# MCU.net
KiCad netlist of a schematic drawn in Altium Designer
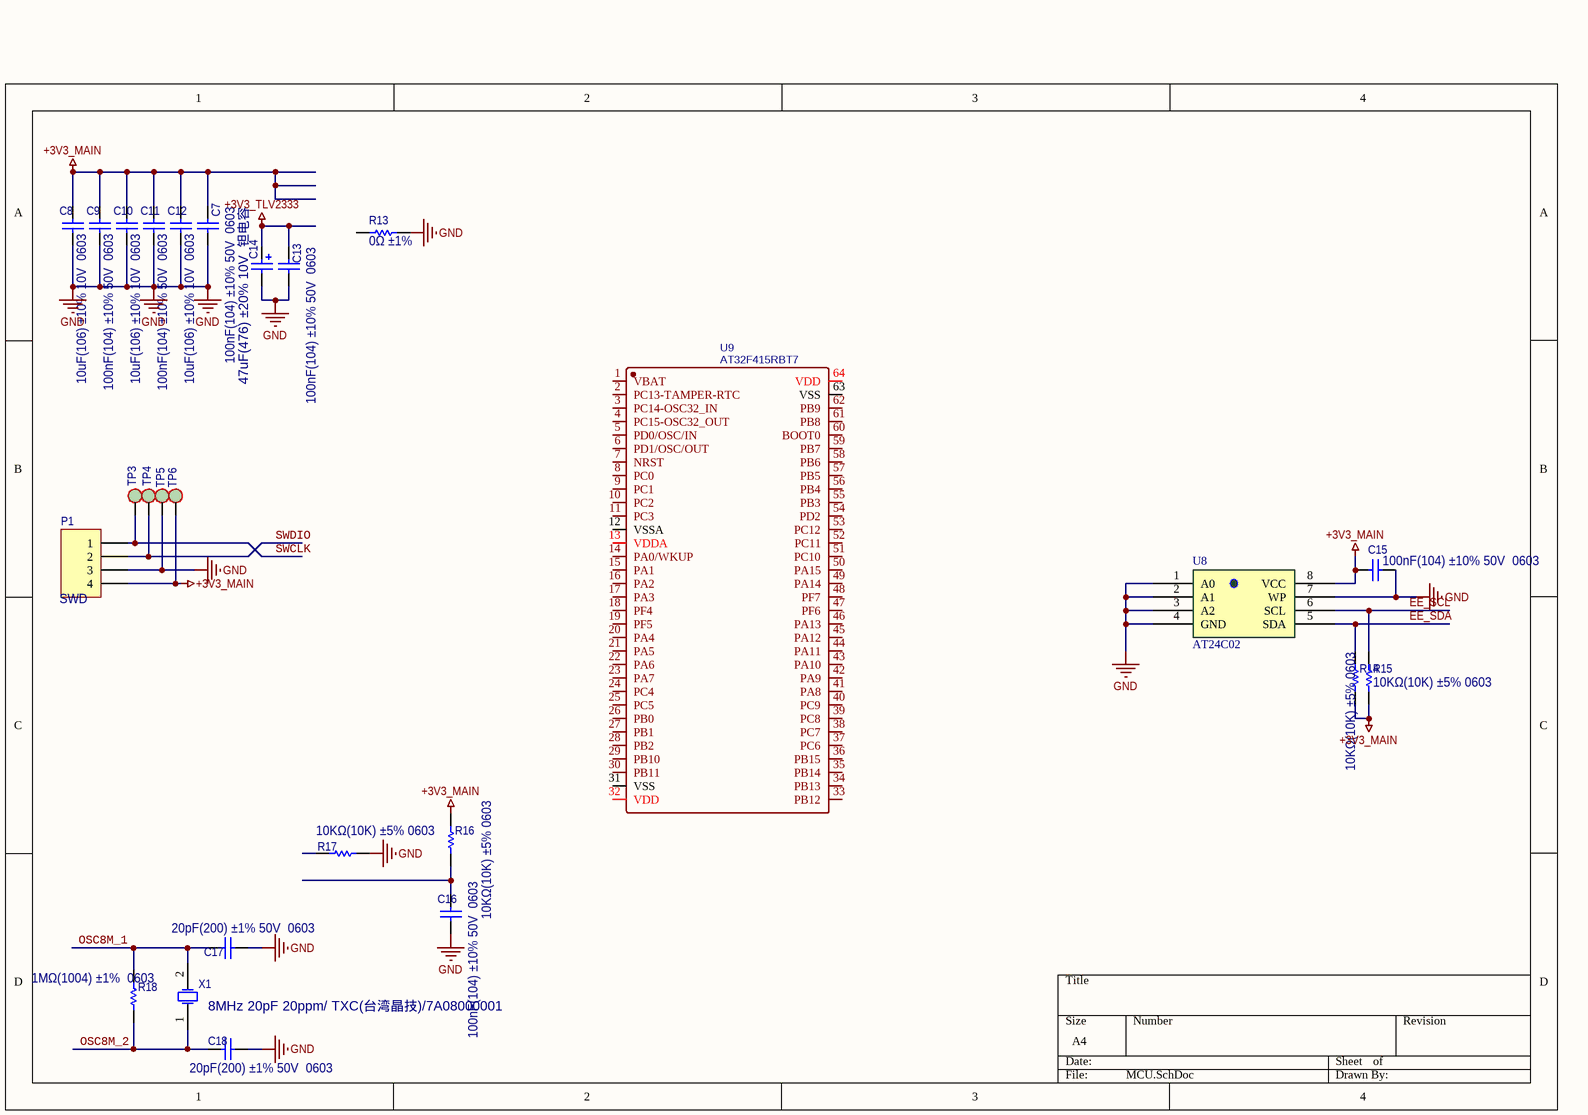
[diagram p0: MCU.SchDoc]

(export (version "E")
  (design (tool "Eeschema 10.0.6"))
  (components
    (comp (ref "C7")
      (value "100nF(104) ±10% 50V  0603")
      (footprint "C0603")
      (description "0603贴片电容")
      (fields (field (name "PUBLISHER") "Altium Limited"))
      (libsource (lib "Miscellaneous Devices") (part "Cap"))
    )
    (comp (ref "C8")
      (value "10uF(106) ±10% 10V  0603")
      (footprint "C0603")
      (description "0603贴片电容")
      (fields (field (name "PUBLISHER") "Altium Limited"))
      (libsource (lib "Miscellaneous Devices") (part "Cap"))
    )
    (comp (ref "C9")
      (value "100nF(104) ±10% 50V  0603")
      (footprint "C0603")
      (description "0603贴片电容")
      (fields (field (name "PUBLISHER") "Altium Limited"))
      (libsource (lib "Miscellaneous Devices") (part "Cap"))
    )
    (comp (ref "C10")
      (value "10uF(106) ±10% 10V  0603")
      (footprint "C0603")
      (description "0603贴片电容")
      (fields (field (name "PUBLISHER") "Altium Limited"))
      (libsource (lib "Miscellaneous Devices") (part "Cap"))
    )
    (comp (ref "C11")
      (value "100nF(104) ±10% 50V  0603")
      (footprint "C0603")
      (description "0603贴片电容")
      (fields (field (name "PUBLISHER") "Altium Limited"))
      (libsource (lib "Miscellaneous Devices") (part "Cap"))
    )
    (comp (ref "C12")
      (value "10uF(106) ±10% 10V  0603")
      (footprint "C0603")
      (description "0603贴片电容")
      (fields (field (name "PUBLISHER") "Altium Limited"))
      (libsource (lib "Miscellaneous Devices") (part "Cap"))
    )
    (comp (ref "C13")
      (value "100nF(104) ±10% 50V  0603")
      (footprint "C0603")
      (description "0603贴片电容")
      (fields (field (name "PUBLISHER") "Altium Limited"))
      (libsource (lib "Miscellaneous Devices") (part "Cap"))
    )
    (comp (ref "C14")
      (value "47uF(476) ±20% 10V  钽电容")
      (footprint "CASE-B_3528")
      (description "CASE_B 3528钽电容")
      (fields (field (name "PUBLISHER") "Altium Limited"))
      (libsource (lib "Miscellaneous Devices") (part "Cap Pol2"))
    )
    (comp (ref "C15")
      (value "100nF(104) ±10% 50V  0603")
      (footprint "C0603")
      (description "0603贴片电容")
      (fields (field (name "PUBLISHER") "Altium Limited"))
      (libsource (lib "Miscellaneous Devices") (part "Cap"))
    )
    (comp (ref "C16")
      (value "100nF(104) ±10% 50V  0603")
      (footprint "C0603")
      (description "0603贴片电容")
      (fields (field (name "PUBLISHER") "Altium Limited"))
      (libsource (lib "Miscellaneous Devices") (part "Cap"))
    )
    (comp (ref "C17")
      (value "20pF(200) ±1% 50V  0603")
      (footprint "C0603")
      (description "0603贴片电容")
      (fields (field (name "PUBLISHER") "Altium Limited"))
      (libsource (lib "Miscellaneous Devices") (part "Cap"))
    )
    (comp (ref "C18")
      (value "20pF(200) ±1% 50V  0603")
      (footprint "C0603")
      (description "0603贴片电容")
      (fields (field (name "PUBLISHER") "Altium Limited"))
      (libsource (lib "Miscellaneous Devices") (part "Cap"))
    )
    (comp (ref "P1")
      (value "SWD")
      (footprint "HDR1X4")
      (description "编程下载口")
      (fields (field (name "PUBLISHER") "Altium Limited"))
      (libsource (lib "Miscellaneous Connectors") (part "Header 4"))
    )
    (comp (ref "R13")
      (value "0Ω ±1%")
      (footprint "R0603")
      (description "0603贴片电阻")
      (fields (field (name "PUBLISHER") "Altium Limited"))
      (libsource (lib "Miscellaneous Devices") (part "Res1"))
    )
    (comp (ref "R14")
      (value "10KΩ(10K) ±5% 0603")
      (footprint "R0603")
      (description "0603贴片电阻")
      (fields (field (name "PUBLISHER") "Altium Limited"))
      (libsource (lib "Miscellaneous Devices") (part "Res1"))
    )
    (comp (ref "R15")
      (value "10KΩ(10K) ±5% 0603")
      (footprint "R0603")
      (description "0603贴片电阻")
      (fields (field (name "PUBLISHER") "Altium Limited"))
      (libsource (lib "Miscellaneous Devices") (part "Res1"))
    )
    (comp (ref "R16")
      (value "10KΩ(10K) ±5% 0603")
      (footprint "R0603")
      (description "0603贴片电阻")
      (fields (field (name "PUBLISHER") "Altium Limited"))
      (libsource (lib "Miscellaneous Devices") (part "Res1"))
    )
    (comp (ref "R17")
      (value "10KΩ(10K) ±5% 0603")
      (footprint "R0603")
      (description "0603贴片电阻")
      (fields (field (name "PUBLISHER") "Altium Limited"))
      (libsource (lib "Miscellaneous Devices") (part "Res1"))
    )
    (comp (ref "R18")
      (value "1MΩ(1004) ±1%  0603")
      (footprint "R0603")
      (description "0603贴片电阻")
      (fields (field (name "PUBLISHER") "Altium Limited"))
      (libsource (lib "Miscellaneous Devices") (part "Res1"))
    )
    (comp (ref "TP3") (value "NC") (footprint "TP") (description "测试点") (libsource (lib "Tek") (part "TP")))
    (comp (ref "TP4") (value "NC") (footprint "TP") (description "测试点") (libsource (lib "Tek") (part "TP")))
    (comp (ref "TP5") (value "NC") (footprint "TP") (description "测试点") (libsource (lib "Tek") (part "TP")))
    (comp (ref "TP6") (value "NC") (footprint "TP") (description "测试点") (libsource (lib "Tek") (part "TP")))
    (comp (ref "U8")
      (value "AT24C02")
      (footprint "SOIC-8_150mil")
      (description "非易失性存储器(ROM)")
      (libsource (lib "Tek") (part "24CXX"))
    )
    (comp (ref "U9")
      (value "AT32F415RBT7")
      (footprint "LQFP64")
      (fields (field (name "BOM_SUPPLIER PART") "C528433") (field (name "CONTRIBUTOR") "LCSC"))
      (libsource (lib "altium-import") (part "root_0_AT32F415RBT7_"))
    )
    (comp (ref "X1")
      (value "8MHz 20pF 20ppm/ TXC(台湾晶技)/7A08000001")
      (footprint "CRY5032_2P_SMT")
      (description "无源晶振  SMD-5032_2P")
      (fields (field (name "PUBLISHER") "ZL_A0OFFICE"))
      (libsource (lib "CommomDevices") (part "XTAL_SMD"))
    )
  )
  (nets
    (net (code "1") (name "+3V3_MAIN") (class "Default")
      (node (ref "C10") (pin "2") (pinfunction "2_2") (pintype "passive"))
      (node (ref "C11") (pin "2") (pinfunction "2_2") (pintype "passive"))
      (node (ref "C12") (pin "2") (pinfunction "2_2") (pintype "passive"))
      (node (ref "C15") (pin "2") (pinfunction "2_2") (pintype "passive"))
      (node (ref "C7") (pin "2") (pinfunction "2_2") (pintype "passive"))
      (node (ref "C8") (pin "2") (pinfunction "2_2") (pintype "passive"))
      (node (ref "C9") (pin "2") (pinfunction "2_2") (pintype "passive"))
      (node (ref "P1") (pin "4") (pinfunction "4_4") (pintype "passive"))
      (node (ref "R14") (pin "2") (pinfunction "2_2") (pintype "passive"))
      (node (ref "R15") (pin "2") (pinfunction "2_2") (pintype "passive"))
      (node (ref "R16") (pin "1") (pinfunction "1_1") (pintype "passive"))
      (node (ref "TP6") (pin "1") (pinfunction "0_1") (pintype "passive"))
      (node (ref "U8") (pin "8") (pinfunction "VCC_8") (pintype "passive"))
    )
    (net (code "2") (name "+3V3_TLV2333") (class "Default")
      (node (ref "C13") (pin "2") (pinfunction "2_2") (pintype "passive"))
      (node (ref "C14") (pin "1") (pinfunction "1_1") (pintype "passive"))
    )
    (net (code "3") (name "/EE_SCL") (class "Default")
      (node (ref "R15") (pin "1") (pinfunction "1_1") (pintype "passive"))
      (node (ref "U8") (pin "6") (pinfunction "SCL_6") (pintype "passive"))
    )
    (net (code "4") (name "/EE_SDA") (class "Default")
      (node (ref "R14") (pin "1") (pinfunction "1_1") (pintype "passive"))
      (node (ref "U8") (pin "5") (pinfunction "SDA_5") (pintype "passive"))
    )
    (net (code "5") (name "/OSC8M_1") (class "Default")
      (node (ref "C17") (pin "2") (pinfunction "2_2") (pintype "passive"))
      (node (ref "R18") (pin "1") (pinfunction "1_1") (pintype "passive"))
      (node (ref "X1") (pin "2") (pinfunction "2_2") (pintype "passive"))
    )
    (net (code "6") (name "/OSC8M_2") (class "Default")
      (node (ref "C18") (pin "2") (pinfunction "2_2") (pintype "passive"))
      (node (ref "R18") (pin "2") (pinfunction "2_2") (pintype "passive"))
      (node (ref "X1") (pin "1") (pinfunction "1_1") (pintype "passive"))
    )
    (net (code "7") (name "/SWCLK") (class "Default")
      (node (ref "P1") (pin "1") (pinfunction "1_1") (pintype "passive"))
      (node (ref "TP3") (pin "1") (pinfunction "0_1") (pintype "passive"))
    )
    (net (code "8") (name "/SWDIO") (class "Default")
      (node (ref "P1") (pin "2") (pinfunction "2_2") (pintype "passive"))
      (node (ref "TP4") (pin "1") (pinfunction "0_1") (pintype "passive"))
    )
    (net (code "9") (name "GND") (class "Default")
      (node (ref "C10") (pin "1") (pinfunction "1_1") (pintype "passive"))
      (node (ref "C11") (pin "1") (pinfunction "1_1") (pintype "passive"))
      (node (ref "C12") (pin "1") (pinfunction "1_1") (pintype "passive"))
      (node (ref "C13") (pin "1") (pinfunction "1_1") (pintype "passive"))
      (node (ref "C14") (pin "2") (pinfunction "2_2") (pintype "passive"))
      (node (ref "C15") (pin "1") (pinfunction "1_1") (pintype "passive"))
      (node (ref "C16") (pin "1") (pinfunction "1_1") (pintype "passive"))
      (node (ref "C17") (pin "1") (pinfunction "1_1") (pintype "passive"))
      (node (ref "C18") (pin "1") (pinfunction "1_1") (pintype "passive"))
      (node (ref "C7") (pin "1") (pinfunction "1_1") (pintype "passive"))
      (node (ref "C8") (pin "1") (pinfunction "1_1") (pintype "passive"))
      (node (ref "C9") (pin "1") (pinfunction "1_1") (pintype "passive"))
      (node (ref "P1") (pin "3") (pinfunction "3_3") (pintype "passive"))
      (node (ref "R13") (pin "1") (pinfunction "1_1") (pintype "passive"))
      (node (ref "R17") (pin "1") (pinfunction "1_1") (pintype "passive"))
      (node (ref "TP5") (pin "1") (pinfunction "0_1") (pintype "passive"))
      (node (ref "U8") (pin "1") (pinfunction "A0_1") (pintype "passive"))
      (node (ref "U8") (pin "2") (pinfunction "A1_2") (pintype "passive"))
      (node (ref "U8") (pin "3") (pinfunction "A2_3") (pintype "passive"))
      (node (ref "U8") (pin "4") (pinfunction "GND_4") (pintype "passive"))
      (node (ref "U8") (pin "7") (pinfunction "WP_7") (pintype "passive"))
    )
    (net (code "10") (name "Net-(C16-Pad2)") (class "Default")
      (node (ref "C16") (pin "2") (pinfunction "2_2") (pintype "passive"))
      (node (ref "R16") (pin "2") (pinfunction "2_2") (pintype "passive"))
    )
    (net (code "11") (name "unconnected-(R13-Pad2)") (class "Default")
      (node (ref "R13") (pin "2") (pinfunction "2_2") (pintype "passive"))
    )
    (net (code "12") (name "unconnected-(R17-Pad2)") (class "Default")
      (node (ref "R17") (pin "2") (pinfunction "2_2") (pintype "passive"))
    )
    (net (code "13") (name "unconnected-(U9-BOOT0-Pad60)") (class "Default")
      (node (ref "U9") (pin "60") (pinfunction "BOOT0_60") (pintype "passive"))
    )
    (net (code "14") (name "unconnected-(U9-NRST-Pad7)") (class "Default")
      (node (ref "U9") (pin "7") (pinfunction "NRST_7") (pintype "passive"))
    )
    (net (code "15") (name "unconnected-(U9-PA0{slash}WKUP-Pad14)") (class "Default")
      (node (ref "U9") (pin "14") (pinfunction "PA0/WKUP_14") (pintype "passive"))
    )
    (net (code "16") (name "unconnected-(U9-PA1-Pad15)") (class "Default")
      (node (ref "U9") (pin "15") (pinfunction "PA1_15") (pintype "passive"))
    )
    (net (code "17") (name "unconnected-(U9-PA2-Pad16)") (class "Default")
      (node (ref "U9") (pin "16") (pinfunction "PA2_16") (pintype "passive"))
    )
    (net (code "18") (name "unconnected-(U9-PA3-Pad17)") (class "Default")
      (node (ref "U9") (pin "17") (pinfunction "PA3_17") (pintype "passive"))
    )
    (net (code "19") (name "unconnected-(U9-PA4-Pad20)") (class "Default")
      (node (ref "U9") (pin "20") (pinfunction "PA4_20") (pintype "passive"))
    )
    (net (code "20") (name "unconnected-(U9-PA5-Pad21)") (class "Default")
      (node (ref "U9") (pin "21") (pinfunction "PA5_21") (pintype "passive"))
    )
    (net (code "21") (name "unconnected-(U9-PA6-Pad22)") (class "Default")
      (node (ref "U9") (pin "22") (pinfunction "PA6_22") (pintype "passive"))
    )
    (net (code "22") (name "unconnected-(U9-PA7-Pad23)") (class "Default")
      (node (ref "U9") (pin "23") (pinfunction "PA7_23") (pintype "passive"))
    )
    (net (code "23") (name "unconnected-(U9-PA8-Pad41)") (class "Default")
      (node (ref "U9") (pin "41") (pinfunction "PA8_41") (pintype "passive"))
    )
    (net (code "24") (name "unconnected-(U9-PA9-Pad42)") (class "Default")
      (node (ref "U9") (pin "42") (pinfunction "PA9_42") (pintype "passive"))
    )
    (net (code "25") (name "unconnected-(U9-PA10-Pad43)") (class "Default")
      (node (ref "U9") (pin "43") (pinfunction "PA10_43") (pintype "passive"))
    )
    (net (code "26") (name "unconnected-(U9-PA11-Pad44)") (class "Default")
      (node (ref "U9") (pin "44") (pinfunction "PA11_44") (pintype "passive"))
    )
    (net (code "27") (name "unconnected-(U9-PA12-Pad45)") (class "Default")
      (node (ref "U9") (pin "45") (pinfunction "PA12_45") (pintype "passive"))
    )
    (net (code "28") (name "unconnected-(U9-PA13-Pad46)") (class "Default")
      (node (ref "U9") (pin "46") (pinfunction "PA13_46") (pintype "passive"))
    )
    (net (code "29") (name "unconnected-(U9-PA14-Pad49)") (class "Default")
      (node (ref "U9") (pin "49") (pinfunction "PA14_49") (pintype "passive"))
    )
    (net (code "30") (name "unconnected-(U9-PA15-Pad50)") (class "Default")
      (node (ref "U9") (pin "50") (pinfunction "PA15_50") (pintype "passive"))
    )
    (net (code "31") (name "unconnected-(U9-PB0-Pad26)") (class "Default")
      (node (ref "U9") (pin "26") (pinfunction "PB0_26") (pintype "passive"))
    )
    (net (code "32") (name "unconnected-(U9-PB1-Pad27)") (class "Default")
      (node (ref "U9") (pin "27") (pinfunction "PB1_27") (pintype "passive"))
    )
    (net (code "33") (name "unconnected-(U9-PB2-Pad28)") (class "Default")
      (node (ref "U9") (pin "28") (pinfunction "PB2_28") (pintype "passive"))
    )
    (net (code "34") (name "unconnected-(U9-PB3-Pad55)") (class "Default")
      (node (ref "U9") (pin "55") (pinfunction "PB3_55") (pintype "passive"))
    )
    (net (code "35") (name "unconnected-(U9-PB4-Pad56)") (class "Default")
      (node (ref "U9") (pin "56") (pinfunction "PB4_56") (pintype "passive"))
    )
    (net (code "36") (name "unconnected-(U9-PB5-Pad57)") (class "Default")
      (node (ref "U9") (pin "57") (pinfunction "PB5_57") (pintype "passive"))
    )
    (net (code "37") (name "unconnected-(U9-PB6-Pad58)") (class "Default")
      (node (ref "U9") (pin "58") (pinfunction "PB6_58") (pintype "passive"))
    )
    (net (code "38") (name "unconnected-(U9-PB7-Pad59)") (class "Default")
      (node (ref "U9") (pin "59") (pinfunction "PB7_59") (pintype "passive"))
    )
    (net (code "39") (name "unconnected-(U9-PB8-Pad61)") (class "Default")
      (node (ref "U9") (pin "61") (pinfunction "PB8_61") (pintype "passive"))
    )
    (net (code "40") (name "unconnected-(U9-PB9-Pad62)") (class "Default")
      (node (ref "U9") (pin "62") (pinfunction "PB9_62") (pintype "passive"))
    )
    (net (code "41") (name "unconnected-(U9-PB10-Pad29)") (class "Default")
      (node (ref "U9") (pin "29") (pinfunction "PB10_29") (pintype "passive"))
    )
    (net (code "42") (name "unconnected-(U9-PB11-Pad30)") (class "Default")
      (node (ref "U9") (pin "30") (pinfunction "PB11_30") (pintype "passive"))
    )
    (net (code "43") (name "unconnected-(U9-PB12-Pad33)") (class "Default")
      (node (ref "U9") (pin "33") (pinfunction "PB12_33") (pintype "passive"))
    )
    (net (code "44") (name "unconnected-(U9-PB13-Pad34)") (class "Default")
      (node (ref "U9") (pin "34") (pinfunction "PB13_34") (pintype "passive"))
    )
    (net (code "45") (name "unconnected-(U9-PB14-Pad35)") (class "Default")
      (node (ref "U9") (pin "35") (pinfunction "PB14_35") (pintype "passive"))
    )
    (net (code "46") (name "unconnected-(U9-PB15-Pad36)") (class "Default")
      (node (ref "U9") (pin "36") (pinfunction "PB15_36") (pintype "passive"))
    )
    (net (code "47") (name "unconnected-(U9-PC0-Pad8)") (class "Default")
      (node (ref "U9") (pin "8") (pinfunction "PC0_8") (pintype "passive"))
    )
    (net (code "48") (name "unconnected-(U9-PC1-Pad9)") (class "Default")
      (node (ref "U9") (pin "9") (pinfunction "PC1_9") (pintype "passive"))
    )
    (net (code "49") (name "unconnected-(U9-PC2-Pad10)") (class "Default")
      (node (ref "U9") (pin "10") (pinfunction "PC2_10") (pintype "passive"))
    )
    (net (code "50") (name "unconnected-(U9-PC3-Pad11)") (class "Default")
      (node (ref "U9") (pin "11") (pinfunction "PC3_11") (pintype "passive"))
    )
    (net (code "51") (name "unconnected-(U9-PC4-Pad24)") (class "Default")
      (node (ref "U9") (pin "24") (pinfunction "PC4_24") (pintype "passive"))
    )
    (net (code "52") (name "unconnected-(U9-PC5-Pad25)") (class "Default")
      (node (ref "U9") (pin "25") (pinfunction "PC5_25") (pintype "passive"))
    )
    (net (code "53") (name "unconnected-(U9-PC6-Pad37)") (class "Default")
      (node (ref "U9") (pin "37") (pinfunction "PC6_37") (pintype "passive"))
    )
    (net (code "54") (name "unconnected-(U9-PC7-Pad38)") (class "Default")
      (node (ref "U9") (pin "38") (pinfunction "PC7_38") (pintype "passive"))
    )
    (net (code "55") (name "unconnected-(U9-PC8-Pad39)") (class "Default")
      (node (ref "U9") (pin "39") (pinfunction "PC8_39") (pintype "passive"))
    )
    (net (code "56") (name "unconnected-(U9-PC9-Pad40)") (class "Default")
      (node (ref "U9") (pin "40") (pinfunction "PC9_40") (pintype "passive"))
    )
    (net (code "57") (name "unconnected-(U9-PC10-Pad51)") (class "Default")
      (node (ref "U9") (pin "51") (pinfunction "PC10_51") (pintype "passive"))
    )
    (net (code "58") (name "unconnected-(U9-PC11-Pad52)") (class "Default")
      (node (ref "U9") (pin "52") (pinfunction "PC11_52") (pintype "passive"))
    )
    (net (code "59") (name "unconnected-(U9-PC12-Pad53)") (class "Default")
      (node (ref "U9") (pin "53") (pinfunction "PC12_53") (pintype "passive"))
    )
    (net (code "60") (name "unconnected-(U9-PC13-TAMPER-RTC-Pad2)") (class "Default")
      (node (ref "U9") (pin "2") (pinfunction "PC13-TAMPER-RTC_2") (pintype "passive"))
    )
    (net (code "61") (name "unconnected-(U9-PC14-OSC32_IN-Pad3)") (class "Default")
      (node (ref "U9") (pin "3") (pinfunction "PC14-OSC32_IN_3") (pintype "passive"))
    )
    (net (code "62") (name "unconnected-(U9-PC15-OSC32_OUT-Pad4)") (class "Default")
      (node (ref "U9") (pin "4") (pinfunction "PC15-OSC32_OUT_4") (pintype "passive"))
    )
    (net (code "63") (name "unconnected-(U9-PD0{slash}OSC{slash}IN-Pad5)") (class "Default")
      (node (ref "U9") (pin "5") (pinfunction "PD0/OSC/IN_5") (pintype "passive"))
    )
    (net (code "64") (name "unconnected-(U9-PD1{slash}OSC{slash}OUT-Pad6)") (class "Default")
      (node (ref "U9") (pin "6") (pinfunction "PD1/OSC/OUT_6") (pintype "passive"))
    )
    (net (code "65") (name "unconnected-(U9-PD2-Pad54)") (class "Default")
      (node (ref "U9") (pin "54") (pinfunction "PD2_54") (pintype "passive"))
    )
    (net (code "66") (name "unconnected-(U9-PF4-Pad18)") (class "Default")
      (node (ref "U9") (pin "18") (pinfunction "PF4_18") (pintype "passive"))
    )
    (net (code "67") (name "unconnected-(U9-PF5-Pad19)") (class "Default")
      (node (ref "U9") (pin "19") (pinfunction "PF5_19") (pintype "passive"))
    )
    (net (code "68") (name "unconnected-(U9-PF6-Pad47)") (class "Default")
      (node (ref "U9") (pin "47") (pinfunction "PF6_47") (pintype "passive"))
    )
    (net (code "69") (name "unconnected-(U9-PF7-Pad48)") (class "Default")
      (node (ref "U9") (pin "48") (pinfunction "PF7_48") (pintype "passive"))
    )
    (net (code "70") (name "unconnected-(U9-VBAT-Pad1)") (class "Default")
      (node (ref "U9") (pin "1") (pinfunction "VBAT_1") (pintype "passive"))
    )
    (net (code "71") (name "unconnected-(U9-VDD-Pad32)") (class "Default")
      (node (ref "U9") (pin "32") (pinfunction "VDD_32") (pintype "passive"))
    )
    (net (code "72") (name "unconnected-(U9-VDD-Pad64)") (class "Default")
      (node (ref "U9") (pin "64") (pinfunction "VDD_64") (pintype "passive"))
    )
    (net (code "73") (name "unconnected-(U9-VDDA-Pad13)") (class "Default")
      (node (ref "U9") (pin "13") (pinfunction "VDDA_13") (pintype "passive"))
    )
    (net (code "74") (name "unconnected-(U9-VSS-Pad31)") (class "Default")
      (node (ref "U9") (pin "31") (pinfunction "VSS_31") (pintype "passive"))
    )
    (net (code "75") (name "unconnected-(U9-VSS-Pad63)") (class "Default")
      (node (ref "U9") (pin "63") (pinfunction "VSS_63") (pintype "passive"))
    )
    (net (code "76") (name "unconnected-(U9-VSSA-Pad12)") (class "Default")
      (node (ref "U9") (pin "12") (pinfunction "VSSA_12") (pintype "passive"))
    )
  )
)
